# anet-cap-z-probe-esp8266-ext.net
KiCad netlist of a schematic drawn in EAGLE
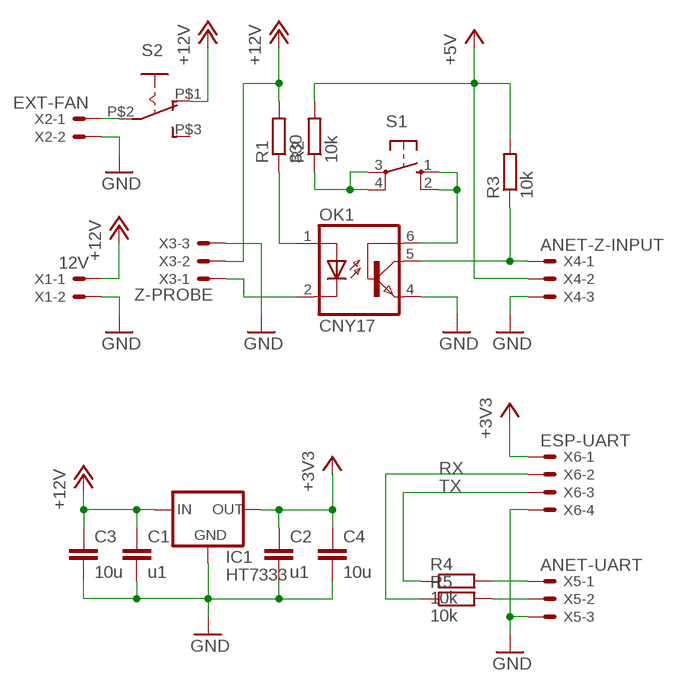
[diagram p0: schematic, sheet 1]

(export (version "E")
  (design (tool "Eeschema 10.0.6"))
  (components
    (comp (ref "C1")
      (value "u1")
      (footprint "eagle-import:C025-025X050")
      (libsource (lib "eagle-import") (part "C-EU025-025X050"))
    )
    (comp (ref "C2")
      (value "u1")
      (footprint "eagle-import:C025-025X050")
      (libsource (lib "eagle-import") (part "C-EU025-025X050"))
    )
    (comp (ref "C3")
      (value "10u")
      (footprint "eagle-import:C0805K")
      (libsource (lib "eagle-import") (part "C-EUC0805K"))
    )
    (comp (ref "C4")
      (value "10u")
      (footprint "eagle-import:C0805K")
      (libsource (lib "eagle-import") (part "C-EUC0805K"))
    )
    (comp (ref "IC1")
      (value "HT7333")
      (footprint "eagle-import:SOT-89")
      (libsource (lib "eagle-import") (part "HT7333"))
    )
    (comp (ref "OK1")
      (value "CNY17")
      (footprint "eagle-import:DIL06")
      (fields (field (name "MPN") "CNY17-1"))
      (libsource (lib "eagle-import") (part "CNY17"))
    )
    (comp (ref "R1")
      (value "330")
      (footprint "eagle-import:R0805")
      (libsource (lib "eagle-import") (part "R-EU_R0805"))
    )
    (comp (ref "R2")
      (value "10k")
      (footprint "eagle-import:R0805")
      (libsource (lib "eagle-import") (part "R-EU_R0805"))
    )
    (comp (ref "R3")
      (value "10k")
      (footprint "eagle-import:R0805")
      (libsource (lib "eagle-import") (part "R-EU_R0805"))
    )
    (comp (ref "R4")
      (value "10k")
      (footprint "eagle-import:0204_7")
      (libsource (lib "eagle-import") (part "R-EU_0204/7"))
    )
    (comp (ref "R5")
      (value "10k")
      (footprint "eagle-import:0204_7")
      (libsource (lib "eagle-import") (part "R-EU_0204/7"))
    )
    (comp (ref "S1")
      (value "10-XX")
      (footprint "eagle-import:B3F-10XX")
      (fields (field (name "MPN") "B3F-1000"))
      (libsource (lib "eagle-import") (part "10-XX"))
    )
    (comp (ref "S2")
      (value "EG1218THIN")
      (footprint "eagle-import:THIN")
      (libsource (lib "eagle-import") (part "EG1218THIN"))
    )
    (comp (ref "X1")
      (value "12V")
      (footprint "eagle-import:JST-XH-02-PACKAGE-LONG-PAD")
      (libsource (lib "eagle-import") (part "JST-XH-02-PIN-LONG-PAD"))
    )
    (comp (ref "X2")
      (value "EXT-FAN")
      (footprint "eagle-import:JST-XH-02-PACKAGE-LONG-PAD")
      (libsource (lib "eagle-import") (part "JST-XH-02-PIN-LONG-PAD"))
    )
    (comp (ref "X3")
      (value "Z-PROBE")
      (footprint "eagle-import:JST-XH-03-PACKAGE-LONG-PAD")
      (libsource (lib "eagle-import") (part "JST-XH-03-PIN-LONG-PAD"))
    )
    (comp (ref "X4")
      (value "ANET-Z-INPUT")
      (footprint "eagle-import:JST-XH-03-PACKAGE-LONG-PAD")
      (libsource (lib "eagle-import") (part "JST-XH-03-PIN-LONG-PAD"))
    )
    (comp (ref "X5")
      (value "ANET-UART")
      (footprint "eagle-import:JST-XH-03-PACKAGE-LONG-PAD")
      (libsource (lib "eagle-import") (part "JST-XH-03-PIN-LONG-PAD"))
    )
    (comp (ref "X6")
      (value "ESP-UART")
      (footprint "eagle-import:JST-XH-04-PACKAGE-LONG-PAD")
      (libsource (lib "eagle-import") (part "JST-XH-04-PIN-LONG-PAD"))
    )
  )
  (nets
    (net (code "1") (name "+3V3") (class "Default")
      (node (ref "C2") (pin "1") (pinfunction "1_1") (pintype "passive"))
      (node (ref "C4") (pin "1") (pinfunction "1_1") (pintype "passive"))
      (node (ref "IC1") (pin "1") (pinfunction "OUT_1") (pintype "passive"))
      (node (ref "X6") (pin "1") (pinfunction "S_1") (pintype "passive"))
    )
    (net (code "2") (name "+5V") (class "Default")
      (node (ref "R2") (pin "2") (pinfunction "2_2") (pintype "passive"))
      (node (ref "R3") (pin "2") (pinfunction "2_2") (pintype "passive"))
      (node (ref "X4") (pin "2") (pinfunction "S_2") (pintype "passive"))
    )
    (net (code "3") (name "+12V") (class "Default")
      (node (ref "C1") (pin "1") (pinfunction "1_1") (pintype "passive"))
      (node (ref "C3") (pin "1") (pinfunction "1_1") (pintype "passive"))
      (node (ref "IC1") (pin "3") (pinfunction "IN_3") (pintype "input"))
      (node (ref "IC1") (pin "4") (pinfunction "IN_4") (pintype "input"))
      (node (ref "R1") (pin "2") (pinfunction "2_2") (pintype "passive"))
      (node (ref "S2") (pin "P$1") (pinfunction "O_P$1") (pintype "passive"))
      (node (ref "X1") (pin "1") (pinfunction "S_1") (pintype "passive"))
      (node (ref "X3") (pin "2") (pinfunction "S_2") (pintype "passive"))
    )
    (net (code "4") (name "/RX") (class "Default")
      (node (ref "R5") (pin "1") (pinfunction "1_1") (pintype "passive"))
      (node (ref "X6") (pin "2") (pinfunction "S_2") (pintype "passive"))
    )
    (net (code "5") (name "/TX") (class "Default")
      (node (ref "R4") (pin "1") (pinfunction "1_1") (pintype "passive"))
      (node (ref "X6") (pin "3") (pinfunction "S_3") (pintype "passive"))
    )
    (net (code "6") (name "GND") (class "Default")
      (node (ref "C1") (pin "2") (pinfunction "2_2") (pintype "passive"))
      (node (ref "C2") (pin "2") (pinfunction "2_2") (pintype "passive"))
      (node (ref "C3") (pin "2") (pinfunction "2_2") (pintype "passive"))
      (node (ref "C4") (pin "2") (pinfunction "2_2") (pintype "passive"))
      (node (ref "IC1") (pin "2") (pinfunction "GND_2") (pintype "input"))
      (node (ref "OK1") (pin "4") (pinfunction "EMI_4") (pintype "passive"))
      (node (ref "X1") (pin "2") (pinfunction "S_2") (pintype "passive"))
      (node (ref "X2") (pin "2") (pinfunction "S_2") (pintype "passive"))
      (node (ref "X3") (pin "3") (pinfunction "S_3") (pintype "passive"))
      (node (ref "X4") (pin "3") (pinfunction "S_3") (pintype "passive"))
      (node (ref "X5") (pin "3") (pinfunction "S_3") (pintype "passive"))
      (node (ref "X6") (pin "4") (pinfunction "S_4") (pintype "passive"))
    )
    (net (code "7") (name "Net-(OK1-A)") (class "Default")
      (node (ref "OK1") (pin "1") (pinfunction "A_1") (pintype "passive"))
      (node (ref "R1") (pin "1") (pinfunction "1_1") (pintype "passive"))
    )
    (net (code "8") (name "Net-(OK1-BAS)") (class "Default")
      (node (ref "OK1") (pin "6") (pinfunction "BAS_6") (pintype "passive"))
      (node (ref "S1") (pin "1") (pinfunction "S_1") (pintype "passive"))
      (node (ref "S1") (pin "2") (pinfunction "S1_2") (pintype "passive"))
    )
    (net (code "9") (name "Net-(OK1-C)") (class "Default")
      (node (ref "OK1") (pin "2") (pinfunction "C_2") (pintype "passive"))
      (node (ref "X3") (pin "1") (pinfunction "S_1") (pintype "passive"))
    )
    (net (code "10") (name "Net-(OK1-COL)") (class "Default")
      (node (ref "OK1") (pin "5") (pinfunction "COL_5") (pintype "passive"))
      (node (ref "R3") (pin "1") (pinfunction "1_1") (pintype "passive"))
      (node (ref "X4") (pin "1") (pinfunction "S_1") (pintype "passive"))
    )
    (net (code "11") (name "Net-(S1-P)") (class "Default")
      (node (ref "R2") (pin "1") (pinfunction "1_1") (pintype "passive"))
      (node (ref "S1") (pin "3") (pinfunction "P_3") (pintype "passive"))
      (node (ref "S1") (pin "4") (pinfunction "P1_4") (pintype "passive"))
    )
    (net (code "12") (name "Net-(S2-P)") (class "Default")
      (node (ref "S2") (pin "P$2") (pinfunction "P_P$2") (pintype "passive"))
      (node (ref "X2") (pin "1") (pinfunction "S_1") (pintype "passive"))
    )
    (net (code "13") (name "Net-(X5A-S)") (class "Default")
      (node (ref "R4") (pin "2") (pinfunction "2_2") (pintype "passive"))
      (node (ref "X5") (pin "1") (pinfunction "S_1") (pintype "passive"))
    )
    (net (code "14") (name "Net-(X5B-S)") (class "Default")
      (node (ref "R5") (pin "2") (pinfunction "2_2") (pintype "passive"))
      (node (ref "X5") (pin "2") (pinfunction "S_2") (pintype "passive"))
    )
    (net (code "15") (name "unconnected-(S2-S-PadP$3)") (class "Default")
      (node (ref "S2") (pin "P$3") (pinfunction "S_P$3") (pintype "passive"))
    )
  )
)
